# PHOTODIODE.net
KiCad netlist of a schematic drawn in Altium Designer
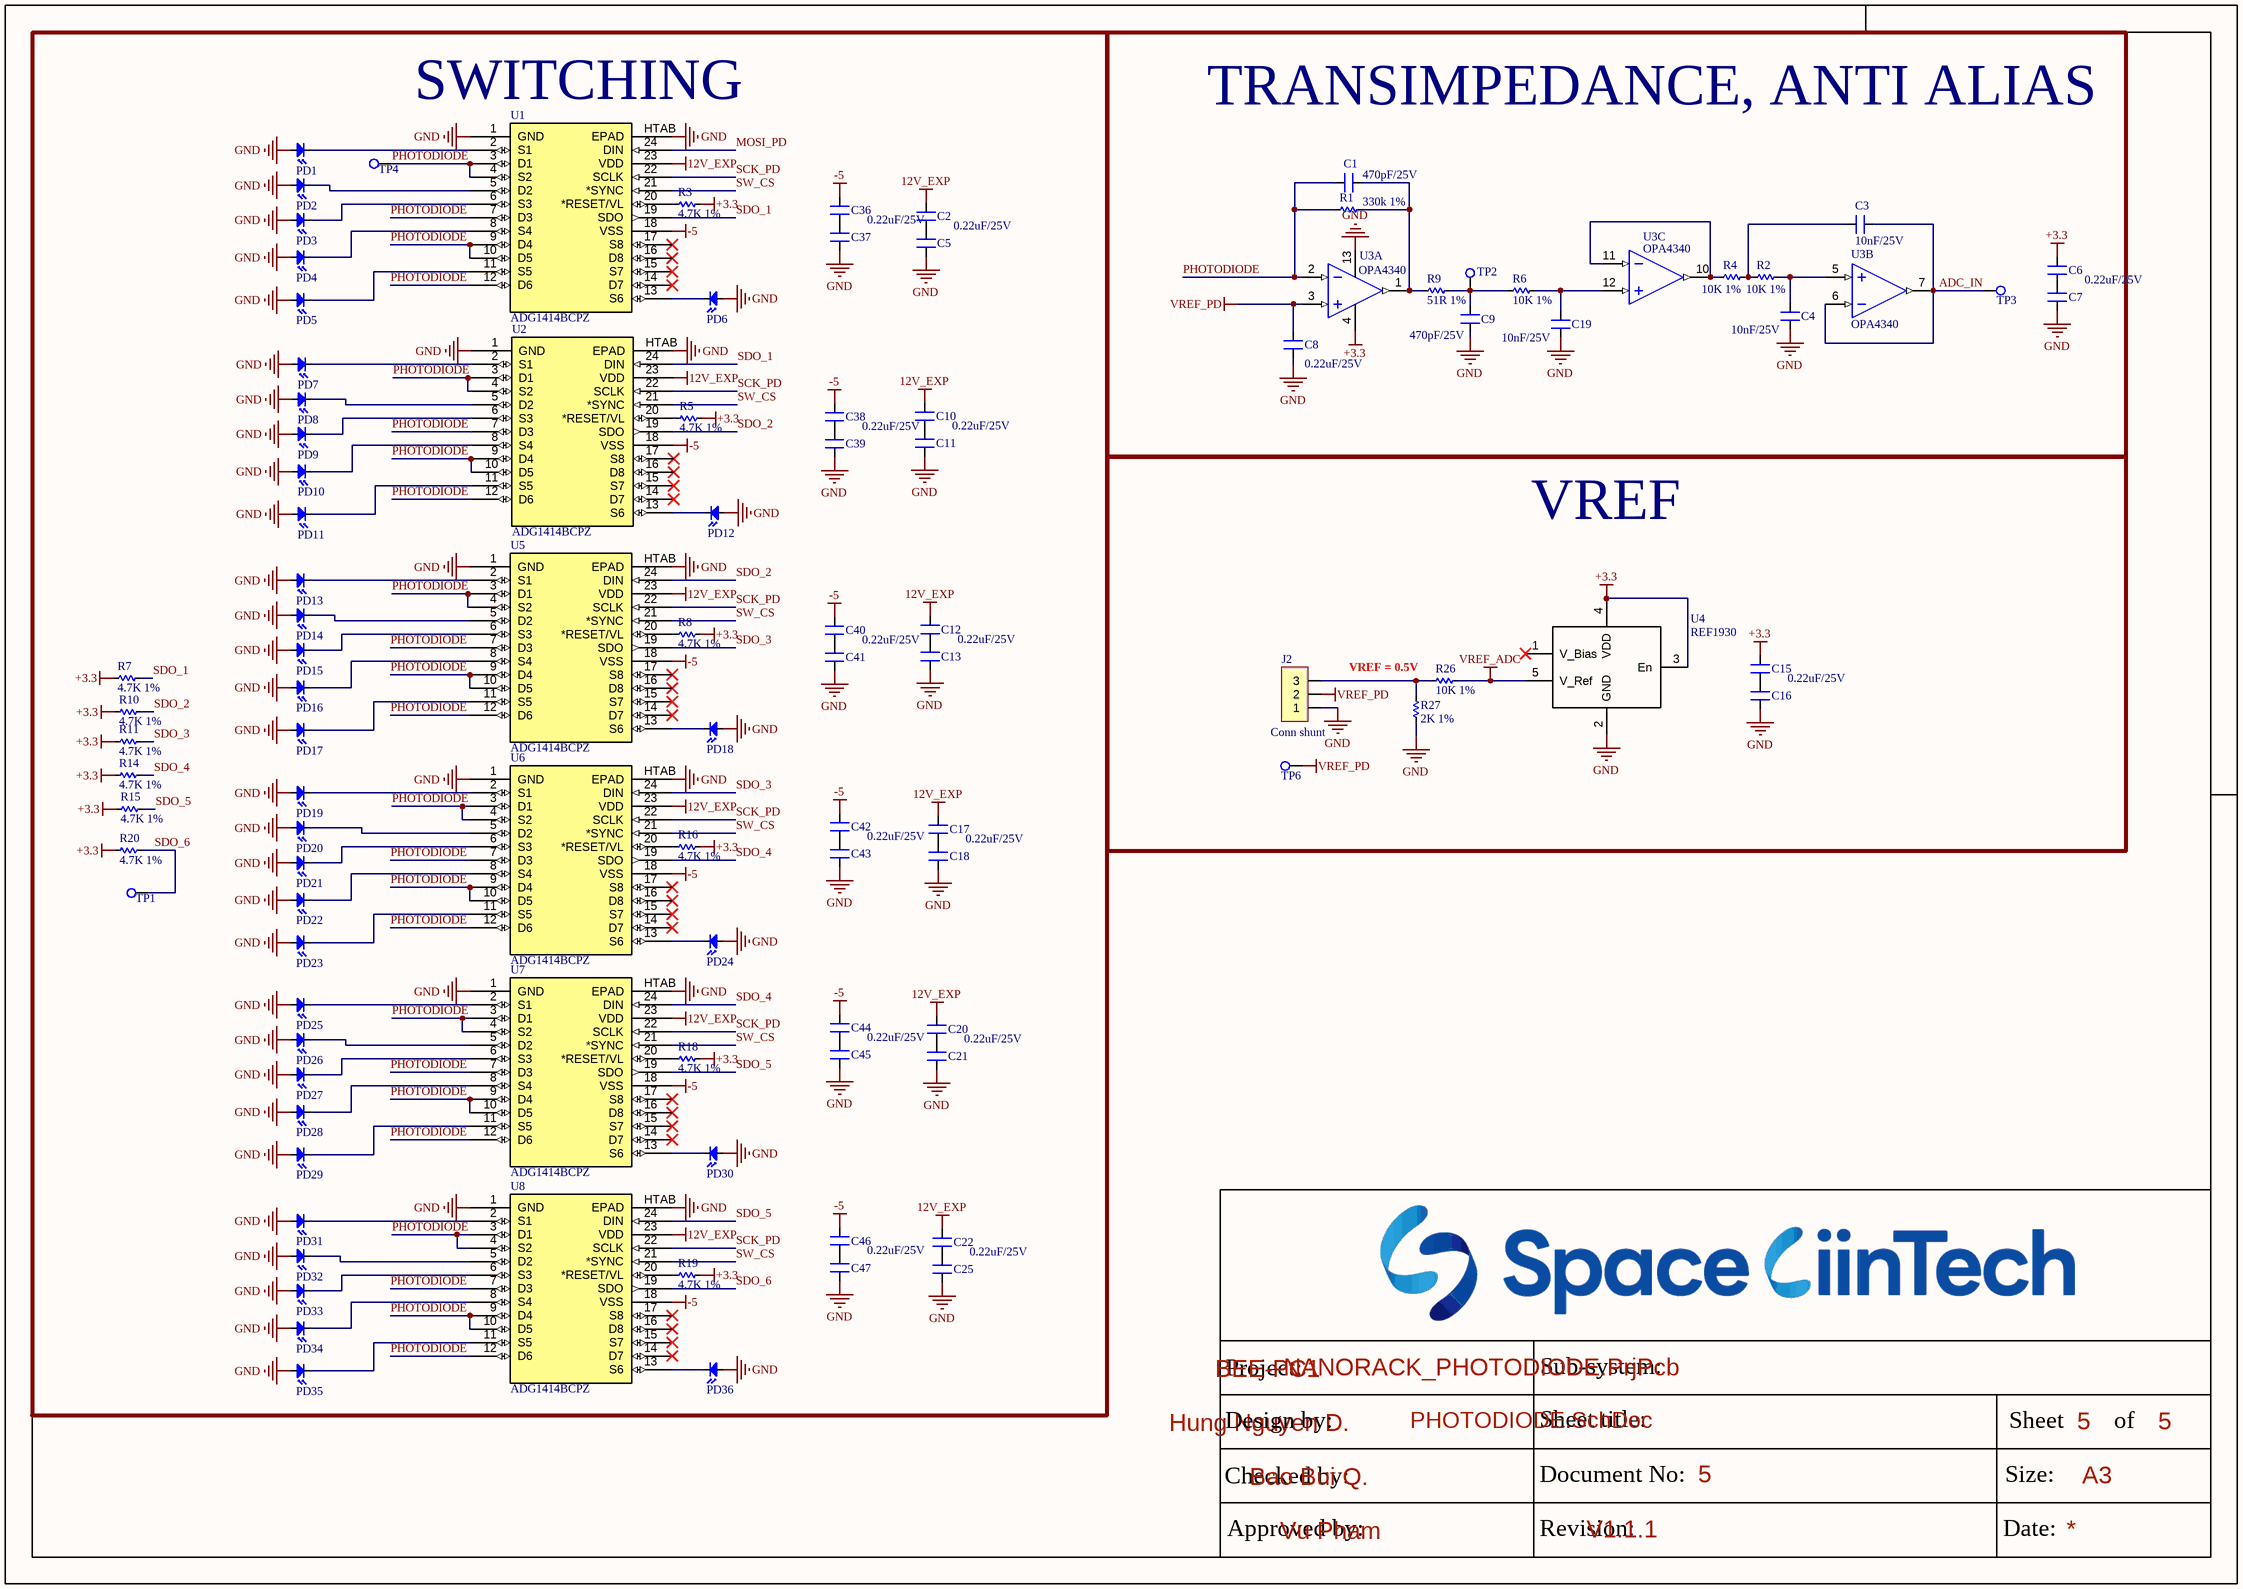
[diagram p0: PHOTODIODE.SchDoc]

(export (version "E")
  (design (tool "Eeschema 10.0.6"))
  (components
    (comp (ref "C1")
      (value "470pF/25V")
      (footprint "CN-SMD-0603")
      (description "0603")
      (libsource (lib "Capacitors") (part "CM"))
    )
    (comp (ref "C2")
      (value "0.22uF/25V")
      (footprint "CN-SMD-0603")
      (description "0603")
      (libsource (lib "Capacitors") (part "CM"))
    )
    (comp (ref "C3")
      (value "10nF/25V")
      (footprint "CN-SMD-0603")
      (description "0603")
      (libsource (lib "Capacitors") (part "CM"))
    )
    (comp (ref "C4")
      (value "10nF/25V")
      (footprint "CN-SMD-0603")
      (description "0603")
      (libsource (lib "Capacitors") (part "CM"))
    )
    (comp (ref "C5")
      (value "0.22uF/25V")
      (footprint "CN-SMD-0603")
      (description "0603")
      (libsource (lib "Capacitors") (part "CM"))
    )
    (comp (ref "C6")
      (value "0.22uF/25V")
      (footprint "CN-SMD-0603")
      (description "0603")
      (libsource (lib "Capacitors") (part "CM"))
    )
    (comp (ref "C7")
      (value "0.22uF/25V")
      (footprint "CN-SMD-0603")
      (description "0603")
      (libsource (lib "Capacitors") (part "CM"))
    )
    (comp (ref "C8")
      (value "0.22uF/25V")
      (footprint "CN-SMD-0603")
      (description "0603")
      (libsource (lib "Capacitors") (part "CM"))
    )
    (comp (ref "C9")
      (value "470pF/25V")
      (footprint "CN-SMD-0603")
      (description "0603")
      (libsource (lib "Capacitors") (part "CM"))
    )
    (comp (ref "C10")
      (value "0.22uF/25V")
      (footprint "CN-SMD-0603")
      (description "0603")
      (libsource (lib "Capacitors") (part "CM"))
    )
    (comp (ref "C11")
      (value "0.22uF/25V")
      (footprint "CN-SMD-0603")
      (description "0603")
      (libsource (lib "Capacitors") (part "CM"))
    )
    (comp (ref "C12")
      (value "0.22uF/25V")
      (footprint "CN-SMD-0603")
      (description "0603")
      (libsource (lib "Capacitors") (part "CM"))
    )
    (comp (ref "C13")
      (value "0.22uF/25V")
      (footprint "CN-SMD-0603")
      (description "0603")
      (libsource (lib "Capacitors") (part "CM"))
    )
    (comp (ref "C15")
      (value "0.22uF/25V")
      (footprint "CN-SMD-0603")
      (description "0603")
      (libsource (lib "Capacitors") (part "CM"))
    )
    (comp (ref "C16")
      (value "0.22uF/25V")
      (footprint "CN-SMD-0603")
      (description "0603")
      (libsource (lib "Capacitors") (part "CM"))
    )
    (comp (ref "C17")
      (value "0.22uF/25V")
      (footprint "CN-SMD-0603")
      (description "0603")
      (libsource (lib "Capacitors") (part "CM"))
    )
    (comp (ref "C18")
      (value "0.22uF/25V")
      (footprint "CN-SMD-0603")
      (description "0603")
      (libsource (lib "Capacitors") (part "CM"))
    )
    (comp (ref "C19")
      (value "10nF/25V")
      (footprint "CN-SMD-0603")
      (description "0603")
      (libsource (lib "Capacitors") (part "CM"))
    )
    (comp (ref "C20")
      (value "0.22uF/25V")
      (footprint "CN-SMD-0603")
      (description "0603")
      (libsource (lib "Capacitors") (part "CM"))
    )
    (comp (ref "C21")
      (value "0.22uF/25V")
      (footprint "CN-SMD-0603")
      (description "0603")
      (libsource (lib "Capacitors") (part "CM"))
    )
    (comp (ref "C22")
      (value "0.22uF/25V")
      (footprint "CN-SMD-0603")
      (description "0603")
      (libsource (lib "Capacitors") (part "CM"))
    )
    (comp (ref "C25")
      (value "0.22uF/25V")
      (footprint "CN-SMD-0603")
      (description "0603")
      (libsource (lib "Capacitors") (part "CM"))
    )
    (comp (ref "C36")
      (value "0.22uF/25V")
      (footprint "CN-SMD-0603")
      (description "0603")
      (libsource (lib "Capacitors") (part "CM"))
    )
    (comp (ref "C37")
      (value "0.22uF/25V")
      (footprint "CN-SMD-0603")
      (description "0603")
      (libsource (lib "Capacitors") (part "CM"))
    )
    (comp (ref "C38")
      (value "0.22uF/25V")
      (footprint "CN-SMD-0603")
      (description "0603")
      (libsource (lib "Capacitors") (part "CM"))
    )
    (comp (ref "C39")
      (value "0.22uF/25V")
      (footprint "CN-SMD-0603")
      (description "0603")
      (libsource (lib "Capacitors") (part "CM"))
    )
    (comp (ref "C40")
      (value "0.22uF/25V")
      (footprint "CN-SMD-0603")
      (description "0603")
      (libsource (lib "Capacitors") (part "CM"))
    )
    (comp (ref "C41")
      (value "0.22uF/25V")
      (footprint "CN-SMD-0603")
      (description "0603")
      (libsource (lib "Capacitors") (part "CM"))
    )
    (comp (ref "C42")
      (value "0.22uF/25V")
      (footprint "CN-SMD-0603")
      (description "0603")
      (libsource (lib "Capacitors") (part "CM"))
    )
    (comp (ref "C43")
      (value "0.22uF/25V")
      (footprint "CN-SMD-0603")
      (description "0603")
      (libsource (lib "Capacitors") (part "CM"))
    )
    (comp (ref "C44")
      (value "0.22uF/25V")
      (footprint "CN-SMD-0603")
      (description "0603")
      (libsource (lib "Capacitors") (part "CM"))
    )
    (comp (ref "C45")
      (value "0.22uF/25V")
      (footprint "CN-SMD-0603")
      (description "0603")
      (libsource (lib "Capacitors") (part "CM"))
    )
    (comp (ref "C46")
      (value "0.22uF/25V")
      (footprint "CN-SMD-0603")
      (description "0603")
      (libsource (lib "Capacitors") (part "CM"))
    )
    (comp (ref "C47")
      (value "0.22uF/25V")
      (footprint "CN-SMD-0603")
      (description "0603")
      (libsource (lib "Capacitors") (part "CM"))
    )
    (comp (ref "J2")
      (value "Conn shunt")
      (footprint "M50-3930342")
      (description "WR-PHD 2.54 mm Angled Socket Header")
      (fields
        (field (name "MANUFACTURER") "Würth Elektronik eiSos GmbH")
        (field (name "PARTNO") "613003143121")
        (field (name "CREATED BY") "Karrer Zheng")
      )
      (libsource (lib "Library") (part "JP3"))
    )
    (comp (ref "PD1")
      (value "Photodiode")
      (footprint "VEMD5080X01")
      (libsource (lib "Library_HUNG") (part "Photodiode"))
    )
    (comp (ref "PD2")
      (value "Photodiode")
      (footprint "VEMD5080X01")
      (libsource (lib "Library_HUNG") (part "Photodiode"))
    )
    (comp (ref "PD3")
      (value "Photodiode")
      (footprint "VEMD5080X01")
      (libsource (lib "Library_HUNG") (part "Photodiode"))
    )
    (comp (ref "PD4")
      (value "Photodiode")
      (footprint "VEMD5080X01")
      (libsource (lib "Library_HUNG") (part "Photodiode"))
    )
    (comp (ref "PD5")
      (value "Photodiode")
      (footprint "VEMD5080X01")
      (libsource (lib "Library_HUNG") (part "Photodiode"))
    )
    (comp (ref "PD6")
      (value "Photodiode")
      (footprint "VEMD5080X01")
      (libsource (lib "Library_HUNG") (part "Photodiode"))
    )
    (comp (ref "PD7")
      (value "Photodiode")
      (footprint "VEMD5080X01")
      (libsource (lib "Library_HUNG") (part "Photodiode"))
    )
    (comp (ref "PD8")
      (value "Photodiode")
      (footprint "VEMD5080X01")
      (libsource (lib "Library_HUNG") (part "Photodiode"))
    )
    (comp (ref "PD9")
      (value "Photodiode")
      (footprint "VEMD5080X01")
      (libsource (lib "Library_HUNG") (part "Photodiode"))
    )
    (comp (ref "PD10")
      (value "Photodiode")
      (footprint "VEMD5080X01")
      (libsource (lib "Library_HUNG") (part "Photodiode"))
    )
    (comp (ref "PD11")
      (value "Photodiode")
      (footprint "VEMD5080X01")
      (libsource (lib "Library_HUNG") (part "Photodiode"))
    )
    (comp (ref "PD12")
      (value "Photodiode")
      (footprint "VEMD5080X01")
      (libsource (lib "Library_HUNG") (part "Photodiode"))
    )
    (comp (ref "PD13")
      (value "Photodiode")
      (footprint "VEMD5080X01")
      (libsource (lib "Library_HUNG") (part "Photodiode"))
    )
    (comp (ref "PD14")
      (value "Photodiode")
      (footprint "VEMD5080X01")
      (libsource (lib "Library_HUNG") (part "Photodiode"))
    )
    (comp (ref "PD15")
      (value "Photodiode")
      (footprint "VEMD5080X01")
      (libsource (lib "Library_HUNG") (part "Photodiode"))
    )
    (comp (ref "PD16")
      (value "Photodiode")
      (footprint "VEMD5080X01")
      (libsource (lib "Library_HUNG") (part "Photodiode"))
    )
    (comp (ref "PD17")
      (value "Photodiode")
      (footprint "VEMD5080X01")
      (libsource (lib "Library_HUNG") (part "Photodiode"))
    )
    (comp (ref "PD18")
      (value "Photodiode")
      (footprint "VEMD5080X01")
      (libsource (lib "Library_HUNG") (part "Photodiode"))
    )
    (comp (ref "PD19")
      (value "Photodiode")
      (footprint "VEMD5080X01")
      (libsource (lib "Library_HUNG") (part "Photodiode"))
    )
    (comp (ref "PD20")
      (value "Photodiode")
      (footprint "VEMD5080X01")
      (libsource (lib "Library_HUNG") (part "Photodiode"))
    )
    (comp (ref "PD21")
      (value "Photodiode")
      (footprint "VEMD5080X01")
      (libsource (lib "Library_HUNG") (part "Photodiode"))
    )
    (comp (ref "PD22")
      (value "Photodiode")
      (footprint "VEMD5080X01")
      (libsource (lib "Library_HUNG") (part "Photodiode"))
    )
    (comp (ref "PD23")
      (value "Photodiode")
      (footprint "VEMD5080X01")
      (libsource (lib "Library_HUNG") (part "Photodiode"))
    )
    (comp (ref "PD24")
      (value "Photodiode")
      (footprint "VEMD5080X01")
      (libsource (lib "Library_HUNG") (part "Photodiode"))
    )
    (comp (ref "PD25")
      (value "Photodiode")
      (footprint "VEMD5080X01")
      (libsource (lib "Library_HUNG") (part "Photodiode"))
    )
    (comp (ref "PD26")
      (value "Photodiode")
      (footprint "VEMD5080X01")
      (libsource (lib "Library_HUNG") (part "Photodiode"))
    )
    (comp (ref "PD27")
      (value "Photodiode")
      (footprint "VEMD5080X01")
      (libsource (lib "Library_HUNG") (part "Photodiode"))
    )
    (comp (ref "PD28")
      (value "Photodiode")
      (footprint "VEMD5080X01")
      (libsource (lib "Library_HUNG") (part "Photodiode"))
    )
    (comp (ref "PD29")
      (value "Photodiode")
      (footprint "VEMD5080X01")
      (libsource (lib "Library_HUNG") (part "Photodiode"))
    )
    (comp (ref "PD30")
      (value "Photodiode")
      (footprint "VEMD5080X01")
      (libsource (lib "Library_HUNG") (part "Photodiode"))
    )
    (comp (ref "PD31")
      (value "Photodiode")
      (footprint "VEMD5080X01")
      (libsource (lib "Library_HUNG") (part "Photodiode"))
    )
    (comp (ref "PD32")
      (value "Photodiode")
      (footprint "VEMD5080X01")
      (libsource (lib "Library_HUNG") (part "Photodiode"))
    )
    (comp (ref "PD33")
      (value "Photodiode")
      (footprint "VEMD5080X01")
      (libsource (lib "Library_HUNG") (part "Photodiode"))
    )
    (comp (ref "PD34")
      (value "Photodiode")
      (footprint "VEMD5080X01")
      (libsource (lib "Library_HUNG") (part "Photodiode"))
    )
    (comp (ref "PD35")
      (value "Photodiode")
      (footprint "VEMD5080X01")
      (libsource (lib "Library_HUNG") (part "Photodiode"))
    )
    (comp (ref "PD36")
      (value "Photodiode")
      (footprint "VEMD5080X01")
      (libsource (lib "Library_HUNG") (part "Photodiode"))
    )
    (comp (ref "R1")
      (value "330k 1%")
      (footprint "RES-SMD-0603")
      (description "0603")
      (fields
        (field (name "MANUFACTURER") "Generic Components")
        (field (name "PUBLISHER") "Altium Hobart Technology Centre")
      )
      (libsource (lib "Library") (part "Res-SMD"))
    )
    (comp (ref "R2")
      (value "10K 1%")
      (footprint "RES-SMD-0603")
      (description "0603")
      (fields
        (field (name "MANUFACTURER") "Generic Components")
        (field (name "PUBLISHER") "Altium Hobart Technology Centre")
      )
      (libsource (lib "Library") (part "Res-SMD"))
    )
    (comp (ref "R3")
      (value "4.7K 1%")
      (footprint "RES-SMD-0603")
      (description "0603")
      (fields
        (field (name "MANUFACTURER") "Generic Components")
        (field (name "PUBLISHER") "Altium Hobart Technology Centre")
      )
      (libsource (lib "Library") (part "Res-SMD"))
    )
    (comp (ref "R4")
      (value "10K 1%")
      (footprint "RES-SMD-0603")
      (description "0603")
      (fields
        (field (name "MANUFACTURER") "Generic Components")
        (field (name "PUBLISHER") "Altium Hobart Technology Centre")
      )
      (libsource (lib "Library") (part "Res-SMD"))
    )
    (comp (ref "R5")
      (value "4.7K 1%")
      (footprint "RES-SMD-0603")
      (description "0603")
      (fields
        (field (name "MANUFACTURER") "Generic Components")
        (field (name "PUBLISHER") "Altium Hobart Technology Centre")
      )
      (libsource (lib "Library") (part "Res-SMD"))
    )
    (comp (ref "R6")
      (value "10K 1%")
      (footprint "RES-SMD-0603")
      (description "0603")
      (fields
        (field (name "MANUFACTURER") "Generic Components")
        (field (name "PUBLISHER") "Altium Hobart Technology Centre")
      )
      (libsource (lib "Library") (part "Res-SMD"))
    )
    (comp (ref "R7")
      (value "4.7K 1%")
      (footprint "RES-SMD-0603")
      (description "0603")
      (fields
        (field (name "MANUFACTURER") "Generic Components")
        (field (name "PUBLISHER") "Altium Hobart Technology Centre")
      )
      (libsource (lib "Library") (part "Res-SMD"))
    )
    (comp (ref "R8")
      (value "4.7K 1%")
      (footprint "RES-SMD-0603")
      (description "0603")
      (fields
        (field (name "MANUFACTURER") "Generic Components")
        (field (name "PUBLISHER") "Altium Hobart Technology Centre")
      )
      (libsource (lib "Library") (part "Res-SMD"))
    )
    (comp (ref "R9")
      (value "51R 1%")
      (footprint "RES-SMD-0603")
      (description "0603")
      (fields
        (field (name "MANUFACTURER") "Generic Components")
        (field (name "PUBLISHER") "Altium Hobart Technology Centre")
      )
      (libsource (lib "Library") (part "Res-SMD"))
    )
    (comp (ref "R10")
      (value "4.7K 1%")
      (footprint "RES-SMD-0603")
      (description "0603")
      (fields
        (field (name "MANUFACTURER") "Generic Components")
        (field (name "PUBLISHER") "Altium Hobart Technology Centre")
      )
      (libsource (lib "Library") (part "Res-SMD"))
    )
    (comp (ref "R11")
      (value "4.7K 1%")
      (footprint "RES-SMD-0603")
      (description "0603")
      (fields
        (field (name "MANUFACTURER") "Generic Components")
        (field (name "PUBLISHER") "Altium Hobart Technology Centre")
      )
      (libsource (lib "Library") (part "Res-SMD"))
    )
    (comp (ref "R14")
      (value "4.7K 1%")
      (footprint "RES-SMD-0603")
      (description "0603")
      (fields
        (field (name "MANUFACTURER") "Generic Components")
        (field (name "PUBLISHER") "Altium Hobart Technology Centre")
      )
      (libsource (lib "Library") (part "Res-SMD"))
    )
    (comp (ref "R15")
      (value "4.7K 1%")
      (footprint "RES-SMD-0603")
      (description "0603")
      (fields
        (field (name "MANUFACTURER") "Generic Components")
        (field (name "PUBLISHER") "Altium Hobart Technology Centre")
      )
      (libsource (lib "Library") (part "Res-SMD"))
    )
    (comp (ref "R16")
      (value "4.7K 1%")
      (footprint "RES-SMD-0603")
      (description "0603")
      (fields
        (field (name "MANUFACTURER") "Generic Components")
        (field (name "PUBLISHER") "Altium Hobart Technology Centre")
      )
      (libsource (lib "Library") (part "Res-SMD"))
    )
    (comp (ref "R18")
      (value "4.7K 1%")
      (footprint "RES-SMD-0603")
      (description "0603")
      (fields
        (field (name "MANUFACTURER") "Generic Components")
        (field (name "PUBLISHER") "Altium Hobart Technology Centre")
      )
      (libsource (lib "Library") (part "Res-SMD"))
    )
    (comp (ref "R19")
      (value "4.7K 1%")
      (footprint "RES-SMD-0603")
      (description "0603")
      (fields
        (field (name "MANUFACTURER") "Generic Components")
        (field (name "PUBLISHER") "Altium Hobart Technology Centre")
      )
      (libsource (lib "Library") (part "Res-SMD"))
    )
    (comp (ref "R20")
      (value "4.7K 1%")
      (footprint "RES-SMD-0603")
      (description "0603")
      (fields
        (field (name "MANUFACTURER") "Generic Components")
        (field (name "PUBLISHER") "Altium Hobart Technology Centre")
      )
      (libsource (lib "Library") (part "Res-SMD"))
    )
    (comp (ref "R26")
      (value "10K 1%")
      (footprint "RES-SMD-0603")
      (description "0603")
      (fields
        (field (name "MANUFACTURER") "Generic Components")
        (field (name "PUBLISHER") "Altium Hobart Technology Centre")
      )
      (libsource (lib "Library") (part "Res-SMD"))
    )
    (comp (ref "R27")
      (value "2K 1%")
      (footprint "RES-SMD-0603")
      (description "0603")
      (fields
        (field (name "MANUFACTURER") "Generic Components")
        (field (name "PUBLISHER") "Altium Hobart Technology Centre")
      )
      (libsource (lib "Library") (part "Res-SMD"))
    )
    (comp (ref "TP1")
      (value "Test_Point")
      (footprint "TESTPOINT")
      (libsource (lib "Library_HUNG") (part "Test_Point"))
    )
    (comp (ref "TP2")
      (value "Test_Point")
      (footprint "TESTPOINT")
      (libsource (lib "Library_HUNG") (part "Test_Point"))
    )
    (comp (ref "TP3")
      (value "Test_Point")
      (footprint "TESTPOINT")
      (libsource (lib "Library_HUNG") (part "Test_Point"))
    )
    (comp (ref "TP4")
      (value "Test_Point")
      (footprint "TESTPOINT")
      (libsource (lib "Library_HUNG") (part "Test_Point"))
    )
    (comp (ref "TP6")
      (value "Test_Point")
      (footprint "TESTPOINT")
      (libsource (lib "Library_HUNG") (part "Test_Point"))
    )
    (comp (ref "U1")
      (value "ADG1414BCPZ")
      (footprint "ADG1414BCPZ")
      (description "IC SW SPST-NOX8 11.5OHM 24LFCSP")
      (libsource (lib "Library_HUNG") (part "ADG1414"))
    )
    (comp (ref "U2")
      (value "ADG1414BCPZ")
      (footprint "ADG1414BCPZ")
      (description "IC SW SPST-NOX8 11.5OHM 24LFCSP")
      (libsource (lib "Library_HUNG") (part "ADG1414"))
    )
    (comp (ref "U3")
      (value "OPA4340")
      (footprint "SSOP16")
      (description "IC CMOS 4 CIRCUIT 16SSOP")
      (libsource (lib "Library") (part "OPA4340"))
    )
    (comp (ref "U4")
      (value "REF1930")
      (footprint "SOT23-5")
      (description "REF1941AIDDCT")
      (libsource (lib "Library") (part "REF19xx"))
    )
    (comp (ref "U5")
      (value "ADG1414BCPZ")
      (footprint "ADG1414BCPZ")
      (description "IC SW SPST-NOX8 11.5OHM 24LFCSP")
      (libsource (lib "Library_HUNG") (part "ADG1414"))
    )
    (comp (ref "U6")
      (value "ADG1414BCPZ")
      (footprint "ADG1414BCPZ")
      (description "IC SW SPST-NOX8 11.5OHM 24LFCSP")
      (libsource (lib "Library_HUNG") (part "ADG1414"))
    )
    (comp (ref "U7")
      (value "ADG1414BCPZ")
      (footprint "ADG1414BCPZ")
      (description "IC SW SPST-NOX8 11.5OHM 24LFCSP")
      (libsource (lib "Library_HUNG") (part "ADG1414"))
    )
    (comp (ref "U8")
      (value "ADG1414BCPZ")
      (footprint "ADG1414BCPZ")
      (description "IC SW SPST-NOX8 11.5OHM 24LFCSP")
      (libsource (lib "Library_HUNG") (part "ADG1414"))
    )
  )
  (nets
    (net (code "1") (name "+3.3") (class "Default")
      (node (ref "C15") (pin "2") (pinfunction "2_2") (pintype "passive"))
      (node (ref "C6") (pin "2") (pinfunction "2_2") (pintype "passive"))
      (node (ref "R10") (pin "2") (pinfunction "2_2") (pintype "passive"))
      (node (ref "R11") (pin "2") (pinfunction "2_2") (pintype "passive"))
      (node (ref "R14") (pin "2") (pinfunction "2_2") (pintype "passive"))
      (node (ref "R15") (pin "2") (pinfunction "2_2") (pintype "passive"))
      (node (ref "R16") (pin "2") (pinfunction "2_2") (pintype "passive"))
      (node (ref "R18") (pin "2") (pinfunction "2_2") (pintype "passive"))
      (node (ref "R19") (pin "2") (pinfunction "2_2") (pintype "passive"))
      (node (ref "R20") (pin "2") (pinfunction "2_2") (pintype "passive"))
      (node (ref "R3") (pin "2") (pinfunction "2_2") (pintype "passive"))
      (node (ref "R5") (pin "2") (pinfunction "2_2") (pintype "passive"))
      (node (ref "R7") (pin "2") (pinfunction "2_2") (pintype "passive"))
      (node (ref "R8") (pin "2") (pinfunction "2_2") (pintype "passive"))
      (node (ref "U3") (pin "4") (pinfunction "+V_4") (pintype "passive"))
      (node (ref "U4") (pin "3") (pinfunction "En_3") (pintype "passive"))
      (node (ref "U4") (pin "4") (pinfunction "VDD_4") (pintype "passive"))
    )
    (net (code "2") (name "-5") (class "Default")
      (node (ref "C36") (pin "2") (pinfunction "2_2") (pintype "passive"))
      (node (ref "C38") (pin "2") (pinfunction "2_2") (pintype "passive"))
      (node (ref "C40") (pin "2") (pinfunction "2_2") (pintype "passive"))
      (node (ref "C42") (pin "2") (pinfunction "2_2") (pintype "passive"))
      (node (ref "C44") (pin "2") (pinfunction "2_2") (pintype "passive"))
      (node (ref "C46") (pin "2") (pinfunction "2_2") (pintype "passive"))
      (node (ref "U1") (pin "18") (pinfunction "VSS_18") (pintype "power_in"))
      (node (ref "U2") (pin "18") (pinfunction "VSS_18") (pintype "power_in"))
      (node (ref "U5") (pin "18") (pinfunction "VSS_18") (pintype "power_in"))
      (node (ref "U6") (pin "18") (pinfunction "VSS_18") (pintype "power_in"))
      (node (ref "U7") (pin "18") (pinfunction "VSS_18") (pintype "power_in"))
      (node (ref "U8") (pin "18") (pinfunction "VSS_18") (pintype "power_in"))
    )
    (net (code "3") (name "/ADC_IN") (class "Default")
      (node (ref "C3") (pin "1") (pinfunction "1_1") (pintype "passive"))
      (node (ref "TP3") (pin "1") (pintype "power_in"))
      (node (ref "U3") (pin "6") (pinfunction "IN-_6") (pintype "input"))
      (node (ref "U3") (pin "7") (pinfunction "OUT_7") (pintype "output"))
    )
    (net (code "4") (name "/MOSI_PD") (class "Default")
      (node (ref "U1") (pin "24") (pinfunction "DIN_24") (pintype "input"))
    )
    (net (code "5") (name "/PHOTODIODE") (class "Default")
      (node (ref "C1") (pin "1") (pinfunction "1_1") (pintype "passive"))
      (node (ref "R1") (pin "1") (pinfunction "1_1") (pintype "passive"))
      (node (ref "TP4") (pin "1") (pintype "power_in"))
      (node (ref "U1") (pin "10") (pinfunction "D5_10") (pintype "bidirectional"))
      (node (ref "U1") (pin "12") (pinfunction "D6_12") (pintype "bidirectional"))
      (node (ref "U1") (pin "3") (pinfunction "D1_3") (pintype "bidirectional"))
      (node (ref "U1") (pin "4") (pinfunction "S2_4") (pintype "bidirectional"))
      (node (ref "U1") (pin "7") (pinfunction "D3_7") (pintype "bidirectional"))
      (node (ref "U1") (pin "9") (pinfunction "D4_9") (pintype "bidirectional"))
      (node (ref "U2") (pin "10") (pinfunction "D5_10") (pintype "bidirectional"))
      (node (ref "U2") (pin "12") (pinfunction "D6_12") (pintype "bidirectional"))
      (node (ref "U2") (pin "3") (pinfunction "D1_3") (pintype "bidirectional"))
      (node (ref "U2") (pin "4") (pinfunction "S2_4") (pintype "bidirectional"))
      (node (ref "U2") (pin "7") (pinfunction "D3_7") (pintype "bidirectional"))
      (node (ref "U2") (pin "9") (pinfunction "D4_9") (pintype "bidirectional"))
      (node (ref "U3") (pin "2") (pinfunction "IN-_2") (pintype "input"))
      (node (ref "U5") (pin "10") (pinfunction "D5_10") (pintype "bidirectional"))
      (node (ref "U5") (pin "12") (pinfunction "D6_12") (pintype "bidirectional"))
      (node (ref "U5") (pin "3") (pinfunction "D1_3") (pintype "bidirectional"))
      (node (ref "U5") (pin "4") (pinfunction "S2_4") (pintype "bidirectional"))
      (node (ref "U5") (pin "7") (pinfunction "D3_7") (pintype "bidirectional"))
      (node (ref "U5") (pin "9") (pinfunction "D4_9") (pintype "bidirectional"))
      (node (ref "U6") (pin "10") (pinfunction "D5_10") (pintype "bidirectional"))
      (node (ref "U6") (pin "12") (pinfunction "D6_12") (pintype "bidirectional"))
      (node (ref "U6") (pin "3") (pinfunction "D1_3") (pintype "bidirectional"))
      (node (ref "U6") (pin "4") (pinfunction "S2_4") (pintype "bidirectional"))
      (node (ref "U6") (pin "7") (pinfunction "D3_7") (pintype "bidirectional"))
      (node (ref "U6") (pin "9") (pinfunction "D4_9") (pintype "bidirectional"))
      (node (ref "U7") (pin "10") (pinfunction "D5_10") (pintype "bidirectional"))
      (node (ref "U7") (pin "12") (pinfunction "D6_12") (pintype "bidirectional"))
      (node (ref "U7") (pin "3") (pinfunction "D1_3") (pintype "bidirectional"))
      (node (ref "U7") (pin "4") (pinfunction "S2_4") (pintype "bidirectional"))
      (node (ref "U7") (pin "7") (pinfunction "D3_7") (pintype "bidirectional"))
      (node (ref "U7") (pin "9") (pinfunction "D4_9") (pintype "bidirectional"))
      (node (ref "U8") (pin "10") (pinfunction "D5_10") (pintype "bidirectional"))
      (node (ref "U8") (pin "12") (pinfunction "D6_12") (pintype "bidirectional"))
      (node (ref "U8") (pin "3") (pinfunction "D1_3") (pintype "bidirectional"))
      (node (ref "U8") (pin "4") (pinfunction "S2_4") (pintype "bidirectional"))
      (node (ref "U8") (pin "7") (pinfunction "D3_7") (pintype "bidirectional"))
      (node (ref "U8") (pin "9") (pinfunction "D4_9") (pintype "bidirectional"))
    )
    (net (code "6") (name "/SCK_PD") (class "Default")
      (node (ref "U1") (pin "22") (pinfunction "SCLK_22") (pintype "input"))
      (node (ref "U2") (pin "22") (pinfunction "SCLK_22") (pintype "input"))
      (node (ref "U5") (pin "22") (pinfunction "SCLK_22") (pintype "input"))
      (node (ref "U6") (pin "22") (pinfunction "SCLK_22") (pintype "input"))
      (node (ref "U7") (pin "22") (pinfunction "SCLK_22") (pintype "input"))
      (node (ref "U8") (pin "22") (pinfunction "SCLK_22") (pintype "input"))
    )
    (net (code "7") (name "/SDO_1") (class "Default")
      (node (ref "R7") (pin "1") (pinfunction "1_1") (pintype "passive"))
      (node (ref "U1") (pin "19") (pinfunction "SDO_19") (pintype "output"))
      (node (ref "U2") (pin "24") (pinfunction "DIN_24") (pintype "input"))
    )
    (net (code "8") (name "/SDO_2") (class "Default")
      (node (ref "R10") (pin "1") (pinfunction "1_1") (pintype "passive"))
      (node (ref "U2") (pin "19") (pinfunction "SDO_19") (pintype "output"))
      (node (ref "U5") (pin "24") (pinfunction "DIN_24") (pintype "input"))
    )
    (net (code "9") (name "/SDO_3") (class "Default")
      (node (ref "R11") (pin "1") (pinfunction "1_1") (pintype "passive"))
      (node (ref "U5") (pin "19") (pinfunction "SDO_19") (pintype "output"))
      (node (ref "U6") (pin "24") (pinfunction "DIN_24") (pintype "input"))
    )
    (net (code "10") (name "/SDO_4") (class "Default")
      (node (ref "R14") (pin "1") (pinfunction "1_1") (pintype "passive"))
      (node (ref "U6") (pin "19") (pinfunction "SDO_19") (pintype "output"))
      (node (ref "U7") (pin "24") (pinfunction "DIN_24") (pintype "input"))
    )
    (net (code "11") (name "/SDO_5") (class "Default")
      (node (ref "R15") (pin "1") (pinfunction "1_1") (pintype "passive"))
      (node (ref "U7") (pin "19") (pinfunction "SDO_19") (pintype "output"))
      (node (ref "U8") (pin "24") (pinfunction "DIN_24") (pintype "input"))
    )
    (net (code "12") (name "/SDO_6") (class "Default")
      (node (ref "R20") (pin "1") (pinfunction "1_1") (pintype "passive"))
      (node (ref "TP1") (pin "1") (pintype "power_in"))
      (node (ref "U8") (pin "19") (pinfunction "SDO_19") (pintype "output"))
    )
    (net (code "13") (name "/SW_CS") (class "Default")
      (node (ref "U1") (pin "21") (pinfunction "*SYNC_21") (pintype "input"))
      (node (ref "U2") (pin "21") (pinfunction "*SYNC_21") (pintype "input"))
      (node (ref "U5") (pin "21") (pinfunction "*SYNC_21") (pintype "input"))
      (node (ref "U6") (pin "21") (pinfunction "*SYNC_21") (pintype "input"))
      (node (ref "U7") (pin "21") (pinfunction "*SYNC_21") (pintype "input"))
      (node (ref "U8") (pin "21") (pinfunction "*SYNC_21") (pintype "input"))
    )
    (net (code "14") (name "12V_EXP") (class "Default")
      (node (ref "C10") (pin "2") (pinfunction "2_2") (pintype "passive"))
      (node (ref "C12") (pin "2") (pinfunction "2_2") (pintype "passive"))
      (node (ref "C17") (pin "2") (pinfunction "2_2") (pintype "passive"))
      (node (ref "C2") (pin "2") (pinfunction "2_2") (pintype "passive"))
      (node (ref "C20") (pin "2") (pinfunction "2_2") (pintype "passive"))
      (node (ref "C22") (pin "2") (pinfunction "2_2") (pintype "passive"))
      (node (ref "U1") (pin "23") (pinfunction "VDD_23") (pintype "power_in"))
      (node (ref "U2") (pin "23") (pinfunction "VDD_23") (pintype "power_in"))
      (node (ref "U5") (pin "23") (pinfunction "VDD_23") (pintype "power_in"))
      (node (ref "U6") (pin "23") (pinfunction "VDD_23") (pintype "power_in"))
      (node (ref "U7") (pin "23") (pinfunction "VDD_23") (pintype "power_in"))
      (node (ref "U8") (pin "23") (pinfunction "VDD_23") (pintype "power_in"))
    )
    (net (code "15") (name "GND") (class "Default")
      (node (ref "C11") (pin "1") (pinfunction "1_1") (pintype "passive"))
      (node (ref "C13") (pin "1") (pinfunction "1_1") (pintype "passive"))
      (node (ref "C16") (pin "1") (pinfunction "1_1") (pintype "passive"))
      (node (ref "C18") (pin "1") (pinfunction "1_1") (pintype "passive"))
      (node (ref "C19") (pin "1") (pinfunction "1_1") (pintype "passive"))
      (node (ref "C21") (pin "1") (pinfunction "1_1") (pintype "passive"))
      (node (ref "C25") (pin "1") (pinfunction "1_1") (pintype "passive"))
      (node (ref "C37") (pin "1") (pinfunction "1_1") (pintype "passive"))
      (node (ref "C39") (pin "1") (pinfunction "1_1") (pintype "passive"))
      (node (ref "C4") (pin "1") (pinfunction "1_1") (pintype "passive"))
      (node (ref "C41") (pin "1") (pinfunction "1_1") (pintype "passive"))
      (node (ref "C43") (pin "1") (pinfunction "1_1") (pintype "passive"))
      (node (ref "C45") (pin "1") (pinfunction "1_1") (pintype "passive"))
      (node (ref "C47") (pin "1") (pinfunction "1_1") (pintype "passive"))
      (node (ref "C5") (pin "1") (pinfunction "1_1") (pintype "passive"))
      (node (ref "C7") (pin "1") (pinfunction "1_1") (pintype "passive"))
      (node (ref "C8") (pin "1") (pinfunction "1_1") (pintype "passive"))
      (node (ref "C9") (pin "1") (pinfunction "1_1") (pintype "passive"))
      (node (ref "J2") (pin "1") (pinfunction "1_1") (pintype "passive"))
      (node (ref "PD1") (pin "1") (pinfunction "A_1") (pintype "passive"))
      (node (ref "PD10") (pin "1") (pinfunction "A_1") (pintype "passive"))
      (node (ref "PD11") (pin "1") (pinfunction "A_1") (pintype "passive"))
      (node (ref "PD12") (pin "1") (pinfunction "A_1") (pintype "passive"))
      (node (ref "PD13") (pin "1") (pinfunction "A_1") (pintype "passive"))
      (node (ref "PD14") (pin "1") (pinfunction "A_1") (pintype "passive"))
      (node (ref "PD15") (pin "1") (pinfunction "A_1") (pintype "passive"))
      (node (ref "PD16") (pin "1") (pinfunction "A_1") (pintype "passive"))
      (node (ref "PD17") (pin "1") (pinfunction "A_1") (pintype "passive"))
      (node (ref "PD18") (pin "1") (pinfunction "A_1") (pintype "passive"))
      (node (ref "PD19") (pin "1") (pinfunction "A_1") (pintype "passive"))
      (node (ref "PD2") (pin "1") (pinfunction "A_1") (pintype "passive"))
      (node (ref "PD20") (pin "1") (pinfunction "A_1") (pintype "passive"))
      (node (ref "PD21") (pin "1") (pinfunction "A_1") (pintype "passive"))
      (node (ref "PD22") (pin "1") (pinfunction "A_1") (pintype "passive"))
      (node (ref "PD23") (pin "1") (pinfunction "A_1") (pintype "passive"))
      (node (ref "PD24") (pin "1") (pinfunction "A_1") (pintype "passive"))
      (node (ref "PD25") (pin "1") (pinfunction "A_1") (pintype "passive"))
      (node (ref "PD26") (pin "1") (pinfunction "A_1") (pintype "passive"))
      (node (ref "PD27") (pin "1") (pinfunction "A_1") (pintype "passive"))
      (node (ref "PD28") (pin "1") (pinfunction "A_1") (pintype "passive"))
      (node (ref "PD29") (pin "1") (pinfunction "A_1") (pintype "passive"))
      (node (ref "PD3") (pin "1") (pinfunction "A_1") (pintype "passive"))
      (node (ref "PD30") (pin "1") (pinfunction "A_1") (pintype "passive"))
      (node (ref "PD31") (pin "1") (pinfunction "A_1") (pintype "passive"))
      (node (ref "PD32") (pin "1") (pinfunction "A_1") (pintype "passive"))
      (node (ref "PD33") (pin "1") (pinfunction "A_1") (pintype "passive"))
      (node (ref "PD34") (pin "1") (pinfunction "A_1") (pintype "passive"))
      (node (ref "PD35") (pin "1") (pinfunction "A_1") (pintype "passive"))
      (node (ref "PD36") (pin "1") (pinfunction "A_1") (pintype "passive"))
      (node (ref "PD4") (pin "1") (pinfunction "A_1") (pintype "passive"))
      (node (ref "PD5") (pin "1") (pinfunction "A_1") (pintype "passive"))
      (node (ref "PD6") (pin "1") (pinfunction "A_1") (pintype "passive"))
      (node (ref "PD7") (pin "1") (pinfunction "A_1") (pintype "passive"))
      (node (ref "PD8") (pin "1") (pinfunction "A_1") (pintype "passive"))
      (node (ref "PD9") (pin "1") (pinfunction "A_1") (pintype "passive"))
      (node (ref "R27") (pin "1") (pinfunction "1_1") (pintype "passive"))
      (node (ref "U1") (pin "1") (pinfunction "GND_1") (pintype "power_in"))
      (node (ref "U1") (pin "HTAB") (pinfunction "EPAD_HTAB") (pintype "passive"))
      (node (ref "U2") (pin "1") (pinfunction "GND_1") (pintype "power_in"))
      (node (ref "U2") (pin "HTAB") (pinfunction "EPAD_HTAB") (pintype "passive"))
      (node (ref "U3") (pin "13") (pinfunction "-V_13") (pintype "passive"))
      (node (ref "U4") (pin "2") (pinfunction "GND_2") (pintype "passive"))
      (node (ref "U5") (pin "1") (pinfunction "GND_1") (pintype "power_in"))
      (node (ref "U5") (pin "HTAB") (pinfunction "EPAD_HTAB") (pintype "passive"))
      (node (ref "U6") (pin "1") (pinfunction "GND_1") (pintype "power_in"))
      (node (ref "U6") (pin "HTAB") (pinfunction "EPAD_HTAB") (pintype "passive"))
      (node (ref "U7") (pin "1") (pinfunction "GND_1") (pintype "power_in"))
      (node (ref "U7") (pin "HTAB") (pinfunction "EPAD_HTAB") (pintype "passive"))
      (node (ref "U8") (pin "1") (pinfunction "GND_1") (pintype "power_in"))
      (node (ref "U8") (pin "HTAB") (pinfunction "EPAD_HTAB") (pintype "passive"))
    )
    (net (code "16") (name "Net-(C2-Pad1)") (class "Default")
      (node (ref "C2") (pin "1") (pinfunction "1_1") (pintype "passive"))
      (node (ref "C5") (pin "2") (pinfunction "2_2") (pintype "passive"))
    )
    (net (code "17") (name "Net-(C3-Pad2)") (class "Default")
      (node (ref "C3") (pin "2") (pinfunction "2_2") (pintype "passive"))
      (node (ref "R2") (pin "1") (pinfunction "1_1") (pintype "passive"))
      (node (ref "R4") (pin "2") (pinfunction "2_2") (pintype "passive"))
    )
    (net (code "18") (name "Net-(C6-Pad1)") (class "Default")
      (node (ref "C6") (pin "1") (pinfunction "1_1") (pintype "passive"))
      (node (ref "C7") (pin "2") (pinfunction "2_2") (pintype "passive"))
    )
    (net (code "19") (name "Net-(C9-Pad2)") (class "Default")
      (node (ref "C9") (pin "2") (pinfunction "2_2") (pintype "passive"))
      (node (ref "R6") (pin "1") (pinfunction "1_1") (pintype "passive"))
      (node (ref "R9") (pin "2") (pinfunction "2_2") (pintype "passive"))
      (node (ref "TP2") (pin "1") (pintype "power_in"))
    )
    (net (code "20") (name "Net-(C10-Pad1)") (class "Default")
      (node (ref "C10") (pin "1") (pinfunction "1_1") (pintype "passive"))
      (node (ref "C11") (pin "2") (pinfunction "2_2") (pintype "passive"))
    )
    (net (code "21") (name "Net-(C12-Pad1)") (class "Default")
      (node (ref "C12") (pin "1") (pinfunction "1_1") (pintype "passive"))
      (node (ref "C13") (pin "2") (pinfunction "2_2") (pintype "passive"))
    )
    (net (code "22") (name "Net-(C15-Pad1)") (class "Default")
      (node (ref "C15") (pin "1") (pinfunction "1_1") (pintype "passive"))
      (node (ref "C16") (pin "2") (pinfunction "2_2") (pintype "passive"))
    )
    (net (code "23") (name "Net-(C17-Pad1)") (class "Default")
      (node (ref "C17") (pin "1") (pinfunction "1_1") (pintype "passive"))
      (node (ref "C18") (pin "2") (pinfunction "2_2") (pintype "passive"))
    )
    (net (code "24") (name "Net-(C20-Pad1)") (class "Default")
      (node (ref "C20") (pin "1") (pinfunction "1_1") (pintype "passive"))
      (node (ref "C21") (pin "2") (pinfunction "2_2") (pintype "passive"))
    )
    (net (code "25") (name "Net-(C22-Pad1)") (class "Default")
      (node (ref "C22") (pin "1") (pinfunction "1_1") (pintype "passive"))
      (node (ref "C25") (pin "2") (pinfunction "2_2") (pintype "passive"))
    )
    (net (code "26") (name "Net-(C36-Pad1)") (class "Default")
      (node (ref "C36") (pin "1") (pinfunction "1_1") (pintype "passive"))
      (node (ref "C37") (pin "2") (pinfunction "2_2") (pintype "passive"))
    )
    (net (code "27") (name "Net-(C38-Pad1)") (class "Default")
      (node (ref "C38") (pin "1") (pinfunction "1_1") (pintype "passive"))
      (node (ref "C39") (pin "2") (pinfunction "2_2") (pintype "passive"))
    )
    (net (code "28") (name "Net-(C40-Pad1)") (class "Default")
      (node (ref "C40") (pin "1") (pinfunction "1_1") (pintype "passive"))
      (node (ref "C41") (pin "2") (pinfunction "2_2") (pintype "passive"))
    )
    (net (code "29") (name "Net-(C42-Pad1)") (class "Default")
      (node (ref "C42") (pin "1") (pinfunction "1_1") (pintype "passive"))
      (node (ref "C43") (pin "2") (pinfunction "2_2") (pintype "passive"))
    )
    (net (code "30") (name "Net-(C44-Pad1)") (class "Default")
      (node (ref "C44") (pin "1") (pinfunction "1_1") (pintype "passive"))
      (node (ref "C45") (pin "2") (pinfunction "2_2") (pintype "passive"))
    )
    (net (code "31") (name "Net-(C46-Pad1)") (class "Default")
      (node (ref "C46") (pin "1") (pinfunction "1_1") (pintype "passive"))
      (node (ref "C47") (pin "2") (pinfunction "2_2") (pintype "passive"))
    )
    (net (code "32") (name "Net-(J2-Pad3)") (class "Default")
      (node (ref "J2") (pin "3") (pinfunction "3_3") (pintype "passive"))
      (node (ref "R26") (pin "2") (pinfunction "2_2") (pintype "passive"))
      (node (ref "R27") (pin "2") (pinfunction "2_2") (pintype "passive"))
    )
    (net (code "33") (name "Net-(PD1-K)") (class "Default")
      (node (ref "PD1") (pin "2") (pinfunction "K_2") (pintype "passive"))
      (node (ref "U1") (pin "2") (pinfunction "S1_2") (pintype "bidirectional"))
    )
    (net (code "34") (name "Net-(PD2-K)") (class "Default")
      (node (ref "PD2") (pin "2") (pinfunction "K_2") (pintype "passive"))
      (node (ref "U1") (pin "5") (pinfunction "D2_5") (pintype "bidirectional"))
    )
    (net (code "35") (name "Net-(PD3-K)") (class "Default")
      (node (ref "PD3") (pin "2") (pinfunction "K_2") (pintype "passive"))
      (node (ref "U1") (pin "6") (pinfunction "S3_6") (pintype "bidirectional"))
    )
    (net (code "36") (name "Net-(PD4-K)") (class "Default")
      (node (ref "PD4") (pin "2") (pinfunction "K_2") (pintype "passive"))
      (node (ref "U1") (pin "8") (pinfunction "S4_8") (pintype "bidirectional"))
    )
    (net (code "37") (name "Net-(PD5-K)") (class "Default")
      (node (ref "PD5") (pin "2") (pinfunction "K_2") (pintype "passive"))
      (node (ref "U1") (pin "11") (pinfunction "S5_11") (pintype "bidirectional"))
    )
    (net (code "38") (name "Net-(PD6-K)") (class "Default")
      (node (ref "PD6") (pin "2") (pinfunction "K_2") (pintype "passive"))
      (node (ref "U1") (pin "13") (pinfunction "S6_13") (pintype "bidirectional"))
    )
    (net (code "39") (name "Net-(PD7-K)") (class "Default")
      (node (ref "PD7") (pin "2") (pinfunction "K_2") (pintype "passive"))
      (node (ref "U2") (pin "2") (pinfunction "S1_2") (pintype "bidirectional"))
    )
    (net (code "40") (name "Net-(PD8-K)") (class "Default")
      (node (ref "PD8") (pin "2") (pinfunction "K_2") (pintype "passive"))
      (node (ref "U2") (pin "5") (pinfunction "D2_5") (pintype "bidirectional"))
    )
    (net (code "41") (name "Net-(PD9-K)") (class "Default")
      (node (ref "PD9") (pin "2") (pinfunction "K_2") (pintype "passive"))
      (node (ref "U2") (pin "6") (pinfunction "S3_6") (pintype "bidirectional"))
    )
    (net (code "42") (name "Net-(PD10-K)") (class "Default")
      (node (ref "PD10") (pin "2") (pinfunction "K_2") (pintype "passive"))
      (node (ref "U2") (pin "8") (pinfunction "S4_8") (pintype "bidirectional"))
    )
    (net (code "43") (name "Net-(PD11-K)") (class "Default")
      (node (ref "PD11") (pin "2") (pinfunction "K_2") (pintype "passive"))
      (node (ref "U2") (pin "11") (pinfunction "S5_11") (pintype "bidirectional"))
    )
    (net (code "44") (name "Net-(PD12-K)") (class "Default")
      (node (ref "PD12") (pin "2") (pinfunction "K_2") (pintype "passive"))
      (node (ref "U2") (pin "13") (pinfunction "S6_13") (pintype "bidirectional"))
    )
    (net (code "45") (name "Net-(PD13-K)") (class "Default")
      (node (ref "PD13") (pin "2") (pinfunction "K_2") (pintype "passive"))
      (node (ref "U5") (pin "2") (pinfunction "S1_2") (pintype "bidirectional"))
    )
    (net (code "46") (name "Net-(PD14-K)") (class "Default")
      (node (ref "PD14") (pin "2") (pinfunction "K_2") (pintype "passive"))
      (node (ref "U5") (pin "5") (pinfunction "D2_5") (pintype "bidirectional"))
    )
    (net (code "47") (name "Net-(PD15-K)") (class "Default")
      (node (ref "PD15") (pin "2") (pinfunction "K_2") (pintype "passive"))
      (node (ref "U5") (pin "6") (pinfunction "S3_6") (pintype "bidirectional"))
    )
    (net (code "48") (name "Net-(PD16-K)") (class "Default")
      (node (ref "PD16") (pin "2") (pinfunction "K_2") (pintype "passive"))
      (node (ref "U5") (pin "8") (pinfunction "S4_8") (pintype "bidirectional"))
    )
    (net (code "49") (name "Net-(PD17-K)") (class "Default")
      (node (ref "PD17") (pin "2") (pinfunction "K_2") (pintype "passive"))
      (node (ref "U5") (pin "11") (pinfunction "S5_11") (pintype "bidirectional"))
    )
    (net (code "50") (name "Net-(PD18-K)") (class "Default")
      (node (ref "PD18") (pin "2") (pinfunction "K_2") (pintype "passive"))
      (node (ref "U5") (pin "13") (pinfunction "S6_13") (pintype "bidirectional"))
    )
    (net (code "51") (name "Net-(PD19-K)") (class "Default")
      (node (ref "PD19") (pin "2") (pinfunction "K_2") (pintype "passive"))
      (node (ref "U6") (pin "2") (pinfunction "S1_2") (pintype "bidirectional"))
    )
    (net (code "52") (name "Net-(PD20-K)") (class "Default")
      (node (ref "PD20") (pin "2") (pinfunction "K_2") (pintype "passive"))
      (node (ref "U6") (pin "5") (pinfunction "D2_5") (pintype "bidirectional"))
    )
    (net (code "53") (name "Net-(PD21-K)") (class "Default")
      (node (ref "PD21") (pin "2") (pinfunction "K_2") (pintype "passive"))
      (node (ref "U6") (pin "6") (pinfunction "S3_6") (pintype "bidirectional"))
    )
    (net (code "54") (name "Net-(PD22-K)") (class "Default")
      (node (ref "PD22") (pin "2") (pinfunction "K_2") (pintype "passive"))
      (node (ref "U6") (pin "8") (pinfunction "S4_8") (pintype "bidirectional"))
    )
    (net (code "55") (name "Net-(PD23-K)") (class "Default")
      (node (ref "PD23") (pin "2") (pinfunction "K_2") (pintype "passive"))
      (node (ref "U6") (pin "11") (pinfunction "S5_11") (pintype "bidirectional"))
    )
    (net (code "56") (name "Net-(PD24-K)") (class "Default")
      (node (ref "PD24") (pin "2") (pinfunction "K_2") (pintype "passive"))
      (node (ref "U6") (pin "13") (pinfunction "S6_13") (pintype "bidirectional"))
    )
    (net (code "57") (name "Net-(PD25-K)") (class "Default")
      (node (ref "PD25") (pin "2") (pinfunction "K_2") (pintype "passive"))
      (node (ref "U7") (pin "2") (pinfunction "S1_2") (pintype "bidirectional"))
    )
    (net (code "58") (name "Net-(PD26-K)") (class "Default")
      (node (ref "PD26") (pin "2") (pinfunction "K_2") (pintype "passive"))
      (node (ref "U7") (pin "5") (pinfunction "D2_5") (pintype "bidirectional"))
    )
    (net (code "59") (name "Net-(PD27-K)") (class "Default")
      (node (ref "PD27") (pin "2") (pinfunction "K_2") (pintype "passive"))
      (node (ref "U7") (pin "6") (pinfunction "S3_6") (pintype "bidirectional"))
    )
    (net (code "60") (name "Net-(PD28-K)") (class "Default")
      (node (ref "PD28") (pin "2") (pinfunction "K_2") (pintype "passive"))
      (node (ref "U7") (pin "8") (pinfunction "S4_8") (pintype "bidirectional"))
    )
    (net (code "61") (name "Net-(PD29-K)") (class "Default")
      (node (ref "PD29") (pin "2") (pinfunction "K_2") (pintype "passive"))
      (node (ref "U7") (pin "11") (pinfunction "S5_11") (pintype "bidirectional"))
    )
    (net (code "62") (name "Net-(PD30-K)") (class "Default")
      (node (ref "PD30") (pin "2") (pinfunction "K_2") (pintype "passive"))
      (node (ref "U7") (pin "13") (pinfunction "S6_13") (pintype "bidirectional"))
    )
    (net (code "63") (name "Net-(PD31-K)") (class "Default")
      (node (ref "PD31") (pin "2") (pinfunction "K_2") (pintype "passive"))
      (node (ref "U8") (pin "2") (pinfunction "S1_2") (pintype "bidirectional"))
    )
    (net (code "64") (name "Net-(PD32-K)") (class "Default")
      (node (ref "PD32") (pin "2") (pinfunction "K_2") (pintype "passive"))
      (node (ref "U8") (pin "5") (pinfunction "D2_5") (pintype "bidirectional"))
    )
    (net (code "65") (name "Net-(PD33-K)") (class "Default")
      (node (ref "PD33") (pin "2") (pinfunction "K_2") (pintype "passive"))
      (node (ref "U8") (pin "6") (pinfunction "S3_6") (pintype "bidirectional"))
    )
    (net (code "66") (name "Net-(PD34-K)") (class "Default")
      (node (ref "PD34") (pin "2") (pinfunction "K_2") (pintype "passive"))
      (node (ref "U8") (pin "8") (pinfunction "S4_8") (pintype "bidirectional"))
    )
    (net (code "67") (name "Net-(PD35-K)") (class "Default")
      (node (ref "PD35") (pin "2") (pinfunction "K_2") (pintype "passive"))
      (node (ref "U8") (pin "11") (pinfunction "S5_11") (pintype "bidirectional"))
    )
    (net (code "68") (name "Net-(PD36-K)") (class "Default")
      (node (ref "PD36") (pin "2") (pinfunction "K_2") (pintype "passive"))
      (node (ref "U8") (pin "13") (pinfunction "S6_13") (pintype "bidirectional"))
    )
    (net (code "69") (name "Net-(U1-*RESET{slash}VL)") (class "Default")
      (node (ref "R3") (pin "1") (pinfunction "1_1") (pintype "passive"))
      (node (ref "U1") (pin "20") (pinfunction "*RESET/VL_20") (pintype "bidirectional"))
    )
    (net (code "70") (name "Net-(U2-*RESET{slash}VL)") (class "Default")
      (node (ref "R5") (pin "1") (pinfunction "1_1") (pintype "passive"))
      (node (ref "U2") (pin "20") (pinfunction "*RESET/VL_20") (pintype "bidirectional"))
    )
    (net (code "71") (name "Net-(U3A-OUT)") (class "Default")
      (node (ref "C1") (pin "2") (pinfunction "2_2") (pintype "passive"))
      (node (ref "R1") (pin "2") (pinfunction "2_2") (pintype "passive"))
      (node (ref "R9") (pin "1") (pinfunction "1_1") (pintype "passive"))
      (node (ref "U3") (pin "1") (pinfunction "OUT_1") (pintype "output"))
    )
    (net (code "72") (name "Net-(U3B-IN+)") (class "Default")
      (node (ref "C4") (pin "2") (pinfunction "2_2") (pintype "passive"))
      (node (ref "R2") (pin "2") (pinfunction "2_2") (pintype "passive"))
      (node (ref "U3") (pin "5") (pinfunction "IN+_5") (pintype "input"))
    )
    (net (code "73") (name "Net-(U3C-IN+)") (class "Default")
      (node (ref "C19") (pin "2") (pinfunction "2_2") (pintype "passive"))
      (node (ref "R6") (pin "2") (pinfunction "2_2") (pintype "passive"))
      (node (ref "U3") (pin "12") (pinfunction "IN+_12") (pintype "input"))
    )
    (net (code "74") (name "Net-(U3C-IN-)") (class "Default")
      (node (ref "R4") (pin "1") (pinfunction "1_1") (pintype "passive"))
      (node (ref "U3") (pin "10") (pinfunction "OUT_10") (pintype "output"))
      (node (ref "U3") (pin "11") (pinfunction "IN-_11") (pintype "input"))
    )
    (net (code "75") (name "Net-(U5-*RESET{slash}VL)") (class "Default")
      (node (ref "R8") (pin "1") (pinfunction "1_1") (pintype "passive"))
      (node (ref "U5") (pin "20") (pinfunction "*RESET/VL_20") (pintype "bidirectional"))
    )
    (net (code "76") (name "Net-(U6-*RESET{slash}VL)") (class "Default")
      (node (ref "R16") (pin "1") (pinfunction "1_1") (pintype "passive"))
      (node (ref "U6") (pin "20") (pinfunction "*RESET/VL_20") (pintype "bidirectional"))
    )
    (net (code "77") (name "Net-(U7-*RESET{slash}VL)") (class "Default")
      (node (ref "R18") (pin "1") (pinfunction "1_1") (pintype "passive"))
      (node (ref "U7") (pin "20") (pinfunction "*RESET/VL_20") (pintype "bidirectional"))
    )
    (net (code "78") (name "Net-(U8-*RESET{slash}VL)") (class "Default")
      (node (ref "R19") (pin "1") (pinfunction "1_1") (pintype "passive"))
      (node (ref "U8") (pin "20") (pinfunction "*RESET/VL_20") (pintype "bidirectional"))
    )
    (net (code "79") (name "VREF_ADC") (class "Default")
      (node (ref "R26") (pin "1") (pinfunction "1_1") (pintype "passive"))
      (node (ref "U4") (pin "5") (pinfunction "V_Ref_5") (pintype "passive"))
    )
    (net (code "80") (name "VREF_PD") (class "Default")
      (node (ref "C8") (pin "2") (pinfunction "2_2") (pintype "passive"))
      (node (ref "J2") (pin "2") (pinfunction "2_2") (pintype "passive"))
      (node (ref "TP6") (pin "1") (pintype "power_in"))
      (node (ref "U3") (pin "3") (pinfunction "IN+_3") (pintype "input"))
    )
    (net (code "81") (name "unconnected-(U1-D7-Pad14)") (class "Default")
      (node (ref "U1") (pin "14") (pinfunction "D7_14") (pintype "bidirectional+no_connect"))
    )
    (net (code "82") (name "unconnected-(U1-D8-Pad16)") (class "Default")
      (node (ref "U1") (pin "16") (pinfunction "D8_16") (pintype "bidirectional+no_connect"))
    )
    (net (code "83") (name "unconnected-(U1-S7-Pad15)") (class "Default")
      (node (ref "U1") (pin "15") (pinfunction "S7_15") (pintype "bidirectional+no_connect"))
    )
    (net (code "84") (name "unconnected-(U1-S8-Pad17)") (class "Default")
      (node (ref "U1") (pin "17") (pinfunction "S8_17") (pintype "bidirectional+no_connect"))
    )
    (net (code "85") (name "unconnected-(U2-D7-Pad14)") (class "Default")
      (node (ref "U2") (pin "14") (pinfunction "D7_14") (pintype "bidirectional+no_connect"))
    )
    (net (code "86") (name "unconnected-(U2-D8-Pad16)") (class "Default")
      (node (ref "U2") (pin "16") (pinfunction "D8_16") (pintype "bidirectional+no_connect"))
    )
    (net (code "87") (name "unconnected-(U2-S7-Pad15)") (class "Default")
      (node (ref "U2") (pin "15") (pinfunction "S7_15") (pintype "bidirectional+no_connect"))
    )
    (net (code "88") (name "unconnected-(U2-S8-Pad17)") (class "Default")
      (node (ref "U2") (pin "17") (pinfunction "S8_17") (pintype "bidirectional+no_connect"))
    )
    (net (code "89") (name "unconnected-(U4-V_Bias-Pad1)") (class "Default")
      (node (ref "U4") (pin "1") (pinfunction "V_Bias_1") (pintype "passive+no_connect"))
    )
    (net (code "90") (name "unconnected-(U5-D7-Pad14)") (class "Default")
      (node (ref "U5") (pin "14") (pinfunction "D7_14") (pintype "bidirectional+no_connect"))
    )
    (net (code "91") (name "unconnected-(U5-D8-Pad16)") (class "Default")
      (node (ref "U5") (pin "16") (pinfunction "D8_16") (pintype "bidirectional+no_connect"))
    )
    (net (code "92") (name "unconnected-(U5-S7-Pad15)") (class "Default")
      (node (ref "U5") (pin "15") (pinfunction "S7_15") (pintype "bidirectional+no_connect"))
    )
    (net (code "93") (name "unconnected-(U5-S8-Pad17)") (class "Default")
      (node (ref "U5") (pin "17") (pinfunction "S8_17") (pintype "bidirectional+no_connect"))
    )
    (net (code "94") (name "unconnected-(U6-D7-Pad14)") (class "Default")
      (node (ref "U6") (pin "14") (pinfunction "D7_14") (pintype "bidirectional+no_connect"))
    )
    (net (code "95") (name "unconnected-(U6-D8-Pad16)") (class "Default")
      (node (ref "U6") (pin "16") (pinfunction "D8_16") (pintype "bidirectional+no_connect"))
    )
    (net (code "96") (name "unconnected-(U6-S7-Pad15)") (class "Default")
      (node (ref "U6") (pin "15") (pinfunction "S7_15") (pintype "bidirectional+no_connect"))
    )
    (net (code "97") (name "unconnected-(U6-S8-Pad17)") (class "Default")
      (node (ref "U6") (pin "17") (pinfunction "S8_17") (pintype "bidirectional+no_connect"))
    )
    (net (code "98") (name "unconnected-(U7-D7-Pad14)") (class "Default")
      (node (ref "U7") (pin "14") (pinfunction "D7_14") (pintype "bidirectional+no_connect"))
    )
    (net (code "99") (name "unconnected-(U7-D8-Pad16)") (class "Default")
      (node (ref "U7") (pin "16") (pinfunction "D8_16") (pintype "bidirectional+no_connect"))
    )
    (net (code "100") (name "unconnected-(U7-S7-Pad15)") (class "Default")
      (node (ref "U7") (pin "15") (pinfunction "S7_15") (pintype "bidirectional+no_connect"))
    )
    (net (code "101") (name "unconnected-(U7-S8-Pad17)") (class "Default")
      (node (ref "U7") (pin "17") (pinfunction "S8_17") (pintype "bidirectional+no_connect"))
    )
    (net (code "102") (name "unconnected-(U8-D7-Pad14)") (class "Default")
      (node (ref "U8") (pin "14") (pinfunction "D7_14") (pintype "bidirectional+no_connect"))
    )
    (net (code "103") (name "unconnected-(U8-D8-Pad16)") (class "Default")
      (node (ref "U8") (pin "16") (pinfunction "D8_16") (pintype "bidirectional+no_connect"))
    )
    (net (code "104") (name "unconnected-(U8-S7-Pad15)") (class "Default")
      (node (ref "U8") (pin "15") (pinfunction "S7_15") (pintype "bidirectional+no_connect"))
    )
    (net (code "105") (name "unconnected-(U8-S8-Pad17)") (class "Default")
      (node (ref "U8") (pin "17") (pinfunction "S8_17") (pintype "bidirectional+no_connect"))
    )
  )
)
